# ProProject_Quadrotor_Mk2_Controller.net
KiCad netlist of a schematic drawn in EasyEDA Pro
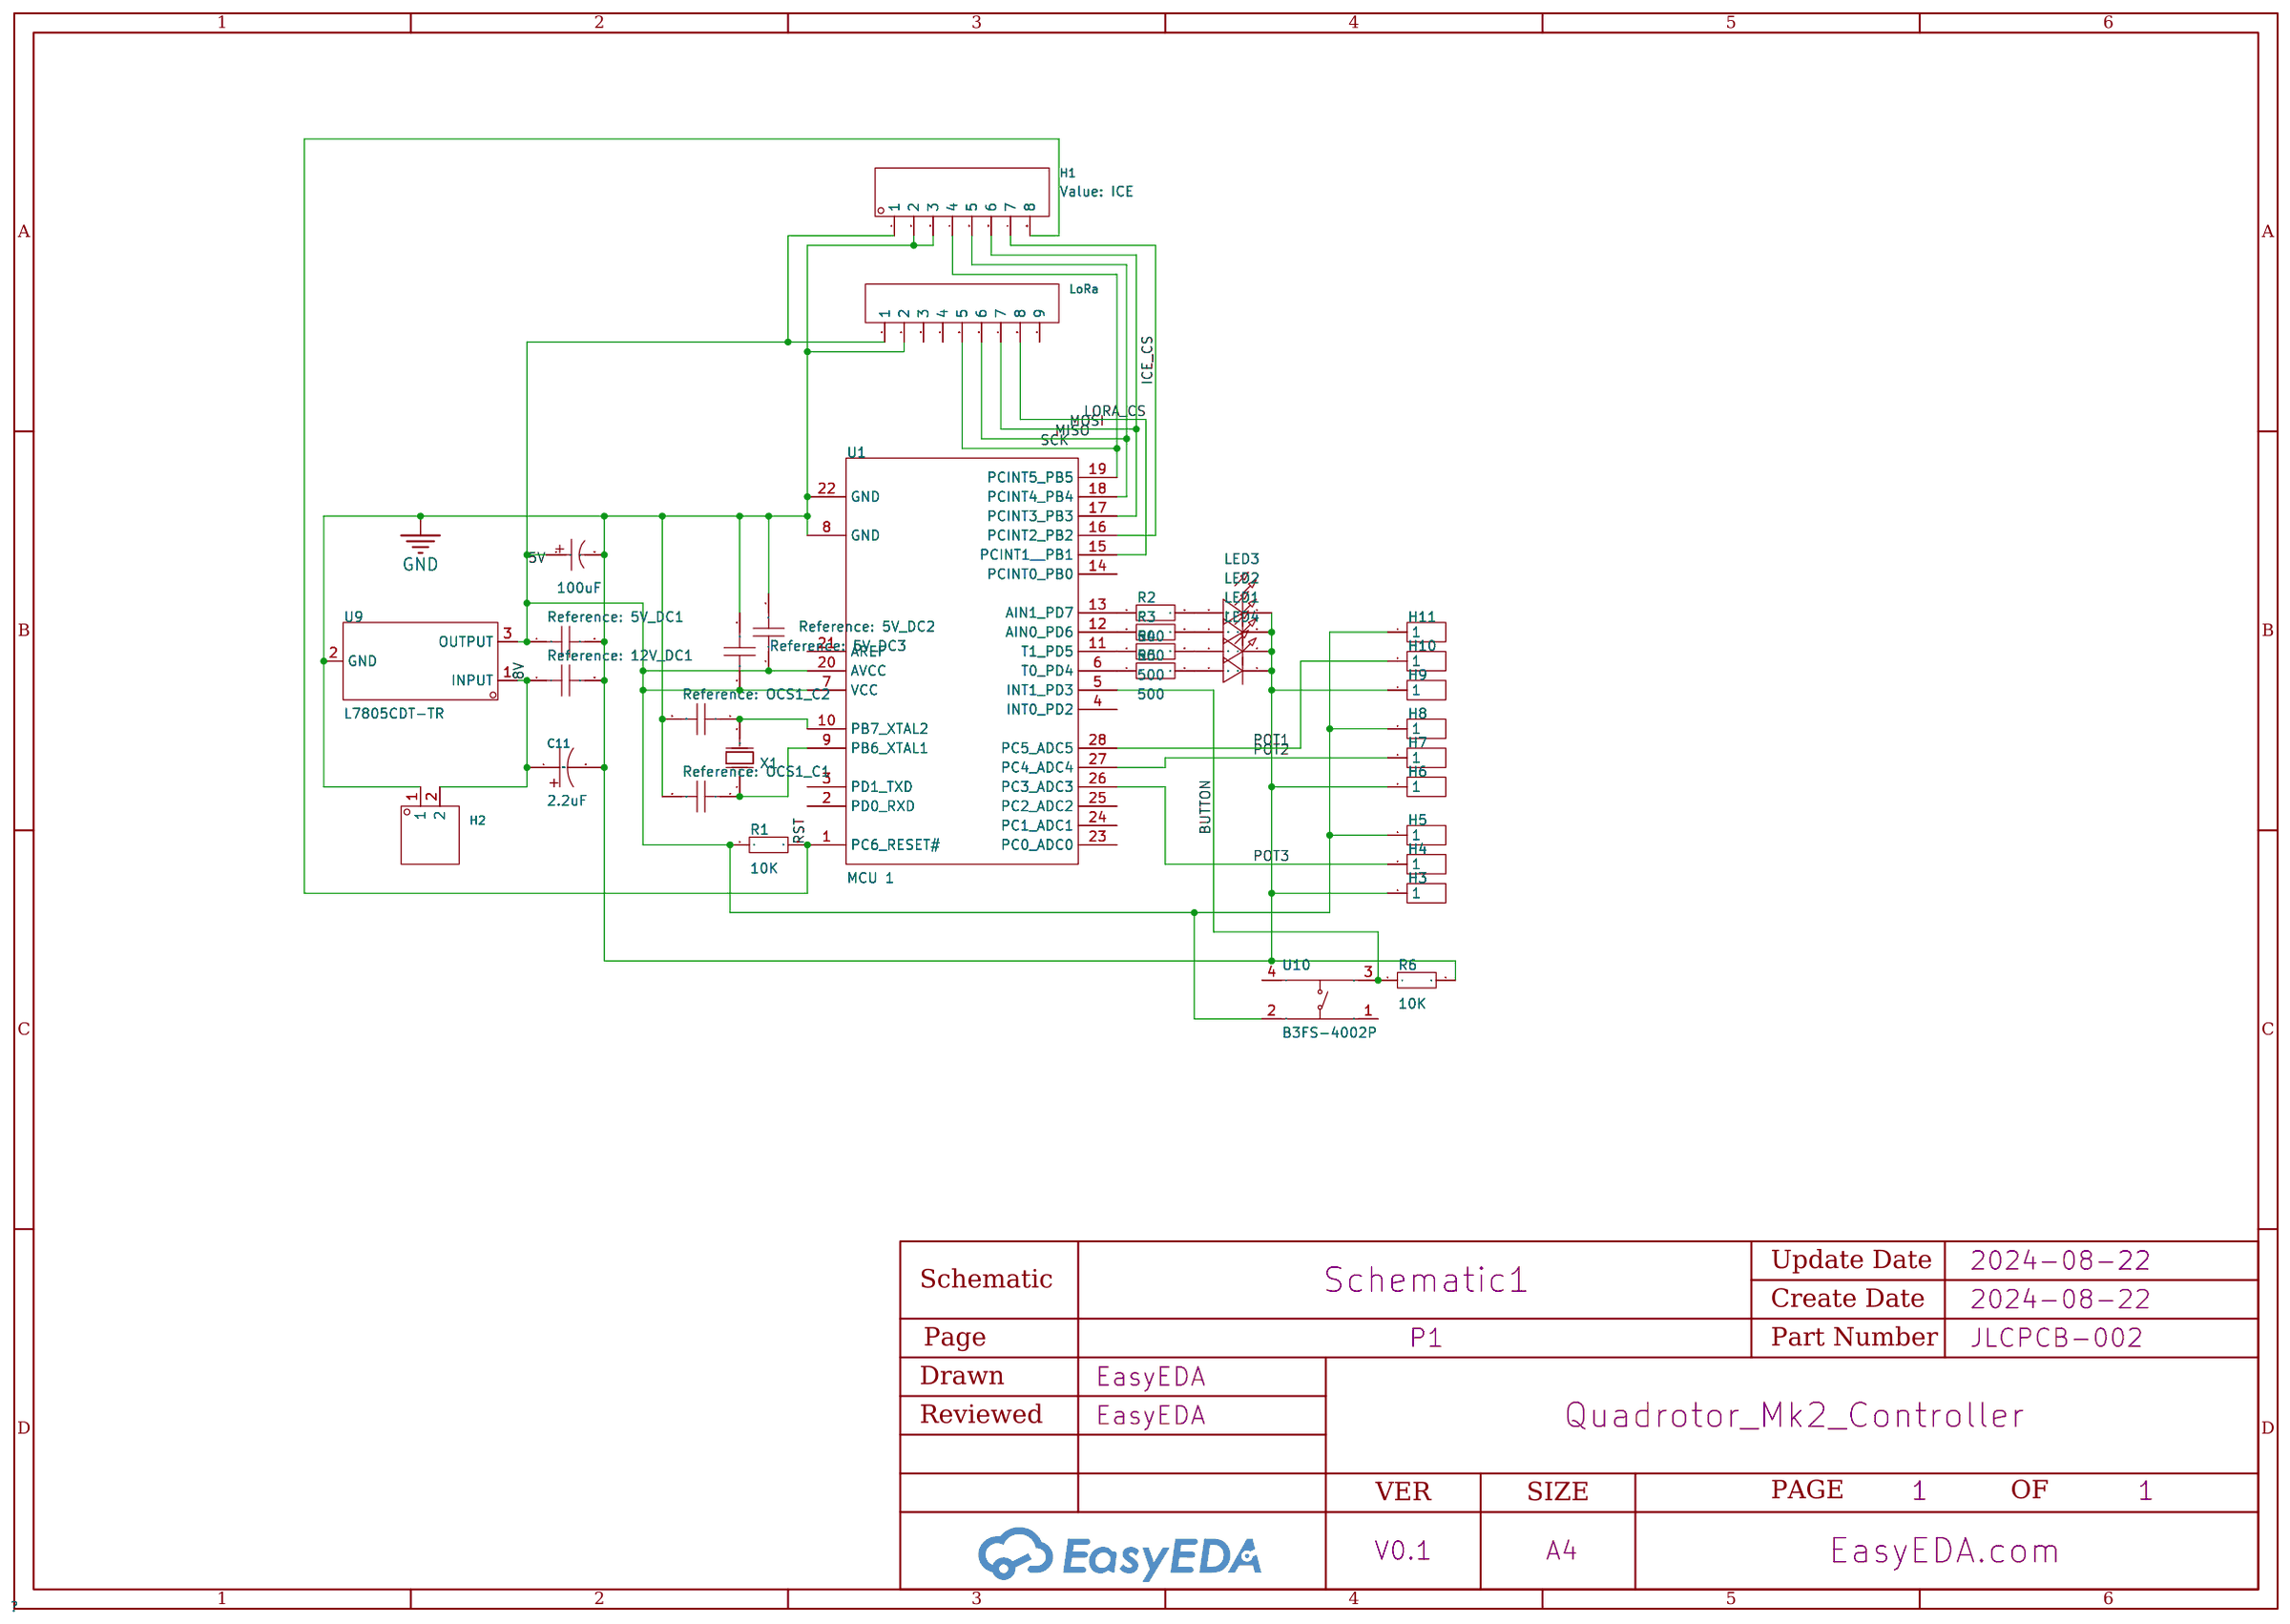
[diagram p0: schematic sheet]

(export (version "E")
  (design (tool "Eeschema 10.0.6"))
  (components
    (comp (ref "5V_DC1")
      (value "100nF")
      (footprint "easyedapro:C0603")
      (libsource (lib "easyedapro") (part "CAP"))
    )
    (comp (ref "5V_DC2")
      (value "100nF")
      (footprint "easyedapro:C0603")
      (libsource (lib "easyedapro") (part "CAP"))
    )
    (comp (ref "5V_DC3")
      (value "100nF")
      (footprint "easyedapro:C0603")
      (libsource (lib "easyedapro") (part "CAP"))
    )
    (comp (ref "12V_DC1")
      (value "100nF")
      (footprint "easyedapro:C0603")
      (libsource (lib "easyedapro") (part "CAP"))
    )
    (comp (ref "C11")
      (value "2.2uF")
      (footprint "easyedapro:CAP-TH_BD5.0-P2.00-D0.8-FD")
      (fields
        (field (name "Manufacturer Part") "RC050M2R2LO5*11TH-2A1E")
        (field (name "Manufacturer") "BERYL(绿宝石)")
      )
      (libsource (lib "easyedapro") (part "RC050M2R2LO5*11TH-2A1E"))
    )
    (comp (ref "C14")
      (value "100uF")
      (footprint "easyedapro:CAP-TH_BD8.0-P3.50-D0.6-FD")
      (fields
        (field (name "Manufacturer Part") "50YXF100MEFC8X11.5")
        (field (name "Manufacturer") "rubycon(红宝石)")
      )
      (libsource (lib "easyedapro") (part "50YXF100MEFC8X11.5"))
    )
    (comp (ref "H1")
      (value "ICE")
      (footprint "easyedapro:HDR-TH_8P-P2.54-V-M")
      (libsource (lib "easyedapro") (part "Header-Male-2.54_1x8"))
    )
    (comp (ref "H2")
      (value "~")
      (footprint "easyedapro:HDR-TH_2P-P2.54-V-M-1")
      (libsource (lib "easyedapro") (part "210S-1*2P L=11.6MMGold-plated black"))
    )
    (comp (ref "H3")
      (value "~")
      (footprint "easyedapro:HDR-TH_1P-V-M_XKB_X4611WV-01I-C28D40")
      (libsource (lib "easyedapro") (part "HDR_1x1"))
    )
    (comp (ref "H4")
      (value "~")
      (footprint "easyedapro:HDR-TH_1P-V-M_XKB_X4611WV-01I-C28D40")
      (libsource (lib "easyedapro") (part "HDR_1x1"))
    )
    (comp (ref "H5")
      (value "~")
      (footprint "easyedapro:HDR-TH_1P-V-M_XKB_X4611WV-01I-C28D40")
      (libsource (lib "easyedapro") (part "HDR_1x1"))
    )
    (comp (ref "H6")
      (value "~")
      (footprint "easyedapro:HDR-TH_1P-V-M_XKB_X4611WV-01I-C28D40")
      (libsource (lib "easyedapro") (part "HDR_1x1"))
    )
    (comp (ref "H7")
      (value "~")
      (footprint "easyedapro:HDR-TH_1P-V-M_XKB_X4611WV-01I-C28D40")
      (libsource (lib "easyedapro") (part "HDR_1x1"))
    )
    (comp (ref "H8")
      (value "~")
      (footprint "easyedapro:HDR-TH_1P-V-M_XKB_X4611WV-01I-C28D40")
      (libsource (lib "easyedapro") (part "HDR_1x1"))
    )
    (comp (ref "H9")
      (value "~")
      (footprint "easyedapro:HDR-TH_1P-V-M_XKB_X4611WV-01I-C28D40")
      (libsource (lib "easyedapro") (part "HDR_1x1"))
    )
    (comp (ref "H10")
      (value "~")
      (footprint "easyedapro:HDR-TH_1P-V-M_XKB_X4611WV-01I-C28D40")
      (libsource (lib "easyedapro") (part "HDR_1x1"))
    )
    (comp (ref "H11")
      (value "~")
      (footprint "easyedapro:HDR-TH_1P-V-M_XKB_X4611WV-01I-C28D40")
      (libsource (lib "easyedapro") (part "HDR_1x1"))
    )
    (comp (ref "LED1")
      (value "~")
      (footprint "easyedapro:LED-TH_BD5.8-P2.54-RD")
      (libsource (lib "easyedapro") (part "LED_TH-G"))
    )
    (comp (ref "LED2")
      (value "~")
      (footprint "easyedapro:LED-TH_BD5.8-P2.54-RD")
      (libsource (lib "easyedapro") (part "LED_TH-G"))
    )
    (comp (ref "LED3")
      (value "~")
      (footprint "easyedapro:LED-TH_BD5.8-P2.54-RD")
      (libsource (lib "easyedapro") (part "LED_TH-G"))
    )
    (comp (ref "LED4")
      (value "~")
      (footprint "easyedapro:LED-TH_BD5.8-P2.54-RD")
      (libsource (lib "easyedapro") (part "LED_TH-G"))
    )
    (comp (ref "LoRa")
      (value "~")
      (footprint "easyedapro:HDR-TH_9P-P2.54-V-F-1")
      (libsource (lib "easyedapro") (part "Header-Female-2.54_1x9"))
    )
    (comp (ref "OCS1_C1")
      (value "22pF")
      (footprint "easyedapro:C0603")
      (libsource (lib "easyedapro") (part "CAP"))
    )
    (comp (ref "OCS1_C2")
      (value "22pF")
      (footprint "easyedapro:C0603")
      (libsource (lib "easyedapro") (part "CAP"))
    )
    (comp (ref "R1") (value "10K") (footprint "easyedapro:R0603") (libsource (lib "easyedapro") (part "Res")))
    (comp (ref "R2") (value "500") (footprint "easyedapro:R0603") (libsource (lib "easyedapro") (part "Res")))
    (comp (ref "R3") (value "500") (footprint "easyedapro:R0603") (libsource (lib "easyedapro") (part "Res")))
    (comp (ref "R4") (value "500") (footprint "easyedapro:R0603") (libsource (lib "easyedapro") (part "Res")))
    (comp (ref "R5") (value "500") (footprint "easyedapro:R0603") (libsource (lib "easyedapro") (part "Res")))
    (comp (ref "R6") (value "10K") (footprint "easyedapro:R0603") (libsource (lib "easyedapro") (part "Res")))
    (comp (ref "U1")
      (value "MCU 1")
      (footprint "easyedapro:DIP-28_L34.6-W7.3-P2.54-LS10.2-BL")
      (fields (field (name "Manufacturer") "MICROCHIP(美国微芯)"))
      (libsource (lib "easyedapro") (part "ATMEGA328P-PU"))
    )
    (comp (ref "U9")
      (value "L7805CDT-TR")
      (footprint "easyedapro:TO-252-3_L6.5-W5.8-P4.58-BL")
      (fields (field (name "Manufacturer") "ST(意法半导体)"))
      (libsource (lib "easyedapro") (part "L7805CDT-TR"))
    )
    (comp (ref "U10")
      (value "B3FS-4002P")
      (footprint "easyedapro:KEY-SMD_4P-L12.0-W12.0-P5.00-LS15.0")
      (fields (field (name "Manufacturer") "OMRON(欧姆龙)"))
      (libsource (lib "easyedapro") (part "B3FS-4002P"))
    )
    (comp (ref "X1")
      (value "20MHz")
      (footprint "easyedapro:OSC-TH_L10.0-W4.5-P5.00")
      (fields (field (name "Manufacturer Part") "49SAC16000182060") (field (name "Manufacturer") "JGHC(晶光华)"))
      (libsource (lib "easyedapro") (part "49SAC16000182060"))
    )
  )
  (nets
    (net (code "1") (name "/5V") (class "Default")
      (node (ref "5V_DC1") (pin "1") (pinfunction "1_1") (pintype "input"))
      (node (ref "5V_DC2") (pin "1") (pinfunction "1_1") (pintype "input"))
      (node (ref "5V_DC3") (pin "1") (pinfunction "1_1") (pintype "input"))
      (node (ref "C14") (pin "1") (pinfunction "1_1") (pintype "input"))
      (node (ref "H1") (pin "1") (pinfunction "1_1") (pintype "input"))
      (node (ref "H11") (pin "1") (pinfunction "1_1") (pintype "unspecified"))
      (node (ref "H5") (pin "1") (pinfunction "1_1") (pintype "unspecified"))
      (node (ref "H8") (pin "1") (pinfunction "1_1") (pintype "unspecified"))
      (node (ref "LoRa") (pin "1") (pinfunction "1_1") (pintype "input"))
      (node (ref "R1") (pin "1") (pinfunction "1_1") (pintype "input"))
      (node (ref "U1") (pin "20") (pinfunction "AVCC_20") (pintype "unspecified"))
      (node (ref "U1") (pin "7") (pinfunction "VCC_7") (pintype "unspecified"))
      (node (ref "U10") (pin "2") (pinfunction "2_2") (pintype "unspecified"))
      (node (ref "U9") (pin "3") (pinfunction "OUTPUT_3") (pintype "unspecified"))
    )
    (net (code "2") (name "/8V") (class "Default")
      (node (ref "12V_DC1") (pin "1") (pinfunction "1_1") (pintype "input"))
      (node (ref "C11") (pin "1") (pinfunction "1_1") (pintype "input"))
      (node (ref "H2") (pin "2") (pinfunction "2_2") (pintype "input"))
      (node (ref "U9") (pin "1") (pinfunction "INPUT_1") (pintype "unspecified"))
    )
    (net (code "3") (name "/BUTTON") (class "Default")
      (node (ref "R6") (pin "1") (pinfunction "1_1") (pintype "input"))
      (node (ref "U1") (pin "5") (pinfunction "INT1_PD3_5") (pintype "bidirectional"))
      (node (ref "U10") (pin "3") (pinfunction "3_3") (pintype "unspecified"))
    )
    (net (code "4") (name "/ICE_CS") (class "Default")
      (node (ref "H1") (pin "7") (pinfunction "7_7") (pintype "input"))
      (node (ref "U1") (pin "16") (pinfunction "PCINT2_PB2_16") (pintype "bidirectional"))
    )
    (net (code "5") (name "/LORA_CS") (class "Default")
      (node (ref "LoRa") (pin "8") (pinfunction "8_8") (pintype "input"))
      (node (ref "U1") (pin "15") (pinfunction "PCINT1__PB1_15") (pintype "bidirectional"))
    )
    (net (code "6") (name "/MISO") (class "Default")
      (node (ref "H1") (pin "5") (pinfunction "5_5") (pintype "input"))
      (node (ref "LoRa") (pin "6") (pinfunction "6_6") (pintype "input"))
      (node (ref "U1") (pin "18") (pinfunction "PCINT4_PB4_18") (pintype "bidirectional"))
    )
    (net (code "7") (name "/MOSI") (class "Default")
      (node (ref "H1") (pin "6") (pinfunction "6_6") (pintype "input"))
      (node (ref "LoRa") (pin "7") (pinfunction "7_7") (pintype "input"))
      (node (ref "U1") (pin "17") (pinfunction "PCINT3_PB3_17") (pintype "bidirectional"))
    )
    (net (code "8") (name "/POT1") (class "Default")
      (node (ref "H10") (pin "1") (pinfunction "1_1") (pintype "unspecified"))
      (node (ref "U1") (pin "28") (pinfunction "PC5_ADC5_28") (pintype "bidirectional"))
    )
    (net (code "9") (name "/POT2") (class "Default")
      (node (ref "H7") (pin "1") (pinfunction "1_1") (pintype "unspecified"))
      (node (ref "U1") (pin "27") (pinfunction "PC4_ADC4_27") (pintype "bidirectional"))
    )
    (net (code "10") (name "/POT3") (class "Default")
      (node (ref "H4") (pin "1") (pinfunction "1_1") (pintype "unspecified"))
      (node (ref "U1") (pin "26") (pinfunction "PC3_ADC3_26") (pintype "bidirectional"))
    )
    (net (code "11") (name "/RST") (class "Default")
      (node (ref "H1") (pin "8") (pinfunction "8_8") (pintype "input"))
      (node (ref "R1") (pin "2") (pinfunction "2_2") (pintype "input"))
      (node (ref "U1") (pin "1") (pinfunction "PC6_RESET#_1") (pintype "bidirectional"))
    )
    (net (code "12") (name "/SCK") (class "Default")
      (node (ref "H1") (pin "4") (pinfunction "4_4") (pintype "input"))
      (node (ref "LoRa") (pin "5") (pinfunction "5_5") (pintype "input"))
      (node (ref "U1") (pin "19") (pinfunction "PCINT5_PB5_19") (pintype "bidirectional"))
    )
    (net (code "13") (name "GND") (class "Default")
      (node (ref "12V_DC1") (pin "2") (pinfunction "2_2") (pintype "input"))
      (node (ref "5V_DC1") (pin "2") (pinfunction "2_2") (pintype "input"))
      (node (ref "5V_DC2") (pin "2") (pinfunction "2_2") (pintype "input"))
      (node (ref "5V_DC3") (pin "2") (pinfunction "2_2") (pintype "input"))
      (node (ref "C11") (pin "2") (pinfunction "2_2") (pintype "input"))
      (node (ref "C14") (pin "2") (pinfunction "2_2") (pintype "input"))
      (node (ref "H1") (pin "2") (pinfunction "2_2") (pintype "input"))
      (node (ref "H1") (pin "3") (pinfunction "3_3") (pintype "input"))
      (node (ref "H2") (pin "1") (pinfunction "1_1") (pintype "input"))
      (node (ref "H3") (pin "1") (pinfunction "1_1") (pintype "unspecified"))
      (node (ref "H6") (pin "1") (pinfunction "1_1") (pintype "unspecified"))
      (node (ref "H9") (pin "1") (pinfunction "1_1") (pintype "unspecified"))
      (node (ref "LED1") (pin "2") (pinfunction "A_2") (pintype "input"))
      (node (ref "LED2") (pin "2") (pinfunction "A_2") (pintype "input"))
      (node (ref "LED3") (pin "2") (pinfunction "A_2") (pintype "input"))
      (node (ref "LED4") (pin "2") (pinfunction "A_2") (pintype "input"))
      (node (ref "LoRa") (pin "2") (pinfunction "2_2") (pintype "input"))
      (node (ref "OCS1_C1") (pin "2") (pinfunction "2_2") (pintype "input"))
      (node (ref "OCS1_C2") (pin "2") (pinfunction "2_2") (pintype "input"))
      (node (ref "R6") (pin "2") (pinfunction "2_2") (pintype "input"))
      (node (ref "U1") (pin "22") (pinfunction "GND_22") (pintype "unspecified"))
      (node (ref "U1") (pin "8") (pinfunction "GND_8") (pintype "unspecified"))
      (node (ref "U9") (pin "2") (pinfunction "GND_2") (pintype "unspecified"))
    )
    (net (code "14") (name "Net-(LED1-C)") (class "Default")
      (node (ref "LED1") (pin "1") (pinfunction "C_1") (pintype "input"))
      (node (ref "R4") (pin "2") (pinfunction "2_2") (pintype "input"))
    )
    (net (code "15") (name "Net-(LED2-C)") (class "Default")
      (node (ref "LED2") (pin "1") (pinfunction "C_1") (pintype "input"))
      (node (ref "R3") (pin "2") (pinfunction "2_2") (pintype "input"))
    )
    (net (code "16") (name "Net-(LED3-C)") (class "Default")
      (node (ref "LED3") (pin "1") (pinfunction "C_1") (pintype "input"))
      (node (ref "R2") (pin "2") (pinfunction "2_2") (pintype "input"))
    )
    (net (code "17") (name "Net-(LED4-C)") (class "Default")
      (node (ref "LED4") (pin "1") (pinfunction "C_1") (pintype "input"))
      (node (ref "R5") (pin "2") (pinfunction "2_2") (pintype "input"))
    )
    (net (code "18") (name "Net-(U1-AIN0_PD6)") (class "Default")
      (node (ref "R3") (pin "1") (pinfunction "1_1") (pintype "input"))
      (node (ref "U1") (pin "12") (pinfunction "AIN0_PD6_12") (pintype "bidirectional"))
    )
    (net (code "19") (name "Net-(U1-AIN1_PD7)") (class "Default")
      (node (ref "R2") (pin "1") (pinfunction "1_1") (pintype "input"))
      (node (ref "U1") (pin "13") (pinfunction "AIN1_PD7_13") (pintype "bidirectional"))
    )
    (net (code "20") (name "Net-(U1-PB6_XTAL1)") (class "Default")
      (node (ref "OCS1_C1") (pin "1") (pinfunction "1_1") (pintype "input"))
      (node (ref "U1") (pin "9") (pinfunction "PB6_XTAL1_9") (pintype "bidirectional"))
      (node (ref "X1") (pin "1") (pinfunction "OSC1_1") (pintype "input"))
    )
    (net (code "21") (name "Net-(U1-PB7_XTAL2)") (class "Default")
      (node (ref "OCS1_C2") (pin "1") (pinfunction "1_1") (pintype "input"))
      (node (ref "U1") (pin "10") (pinfunction "PB7_XTAL2_10") (pintype "bidirectional"))
      (node (ref "X1") (pin "2") (pinfunction "OSC2_2") (pintype "input"))
    )
    (net (code "22") (name "Net-(U1-T0_PD4)") (class "Default")
      (node (ref "R5") (pin "1") (pinfunction "1_1") (pintype "input"))
      (node (ref "U1") (pin "6") (pinfunction "T0_PD4_6") (pintype "bidirectional"))
    )
    (net (code "23") (name "Net-(U1-T1_PD5)") (class "Default")
      (node (ref "R4") (pin "1") (pinfunction "1_1") (pintype "input"))
      (node (ref "U1") (pin "11") (pinfunction "T1_PD5_11") (pintype "bidirectional"))
    )
    (net (code "24") (name "unconnected-(LoRa-Pad3)") (class "Default")
      (node (ref "LoRa") (pin "3") (pinfunction "3_3") (pintype "input"))
    )
    (net (code "25") (name "unconnected-(LoRa-Pad4)") (class "Default")
      (node (ref "LoRa") (pin "4") (pinfunction "4_4") (pintype "input"))
    )
    (net (code "26") (name "unconnected-(LoRa-Pad9)") (class "Default")
      (node (ref "LoRa") (pin "9") (pinfunction "9_9") (pintype "input"))
    )
    (net (code "27") (name "unconnected-(U1-AREF-Pad21)") (class "Default")
      (node (ref "U1") (pin "21") (pinfunction "AREF_21") (pintype "unspecified"))
    )
    (net (code "28") (name "unconnected-(U1-INT0_PD2-Pad4)") (class "Default")
      (node (ref "U1") (pin "4") (pinfunction "INT0_PD2_4") (pintype "bidirectional"))
    )
    (net (code "29") (name "unconnected-(U1-PC0_ADC0-Pad23)") (class "Default")
      (node (ref "U1") (pin "23") (pinfunction "PC0_ADC0_23") (pintype "bidirectional"))
    )
    (net (code "30") (name "unconnected-(U1-PC1_ADC1-Pad24)") (class "Default")
      (node (ref "U1") (pin "24") (pinfunction "PC1_ADC1_24") (pintype "bidirectional"))
    )
    (net (code "31") (name "unconnected-(U1-PC2_ADC2-Pad25)") (class "Default")
      (node (ref "U1") (pin "25") (pinfunction "PC2_ADC2_25") (pintype "bidirectional"))
    )
    (net (code "32") (name "unconnected-(U1-PCINT0_PB0-Pad14)") (class "Default")
      (node (ref "U1") (pin "14") (pinfunction "PCINT0_PB0_14") (pintype "bidirectional"))
    )
    (net (code "33") (name "unconnected-(U1-PD0_RXD-Pad2)") (class "Default")
      (node (ref "U1") (pin "2") (pinfunction "PD0_RXD_2") (pintype "bidirectional"))
    )
    (net (code "34") (name "unconnected-(U1-PD1_TXD-Pad3)") (class "Default")
      (node (ref "U1") (pin "3") (pinfunction "PD1_TXD_3") (pintype "bidirectional"))
    )
    (net (code "35") (name "unconnected-(U10-Pad1)") (class "Default")
      (node (ref "U10") (pin "1") (pinfunction "1_1") (pintype "unspecified"))
    )
    (net (code "36") (name "unconnected-(U10-Pad4)") (class "Default")
      (node (ref "U10") (pin "4") (pinfunction "4_4") (pintype "unspecified"))
    )
  )
)
